# HF_AMP_DRIVER.net
KiCad netlist of a schematic drawn in Altium Designer
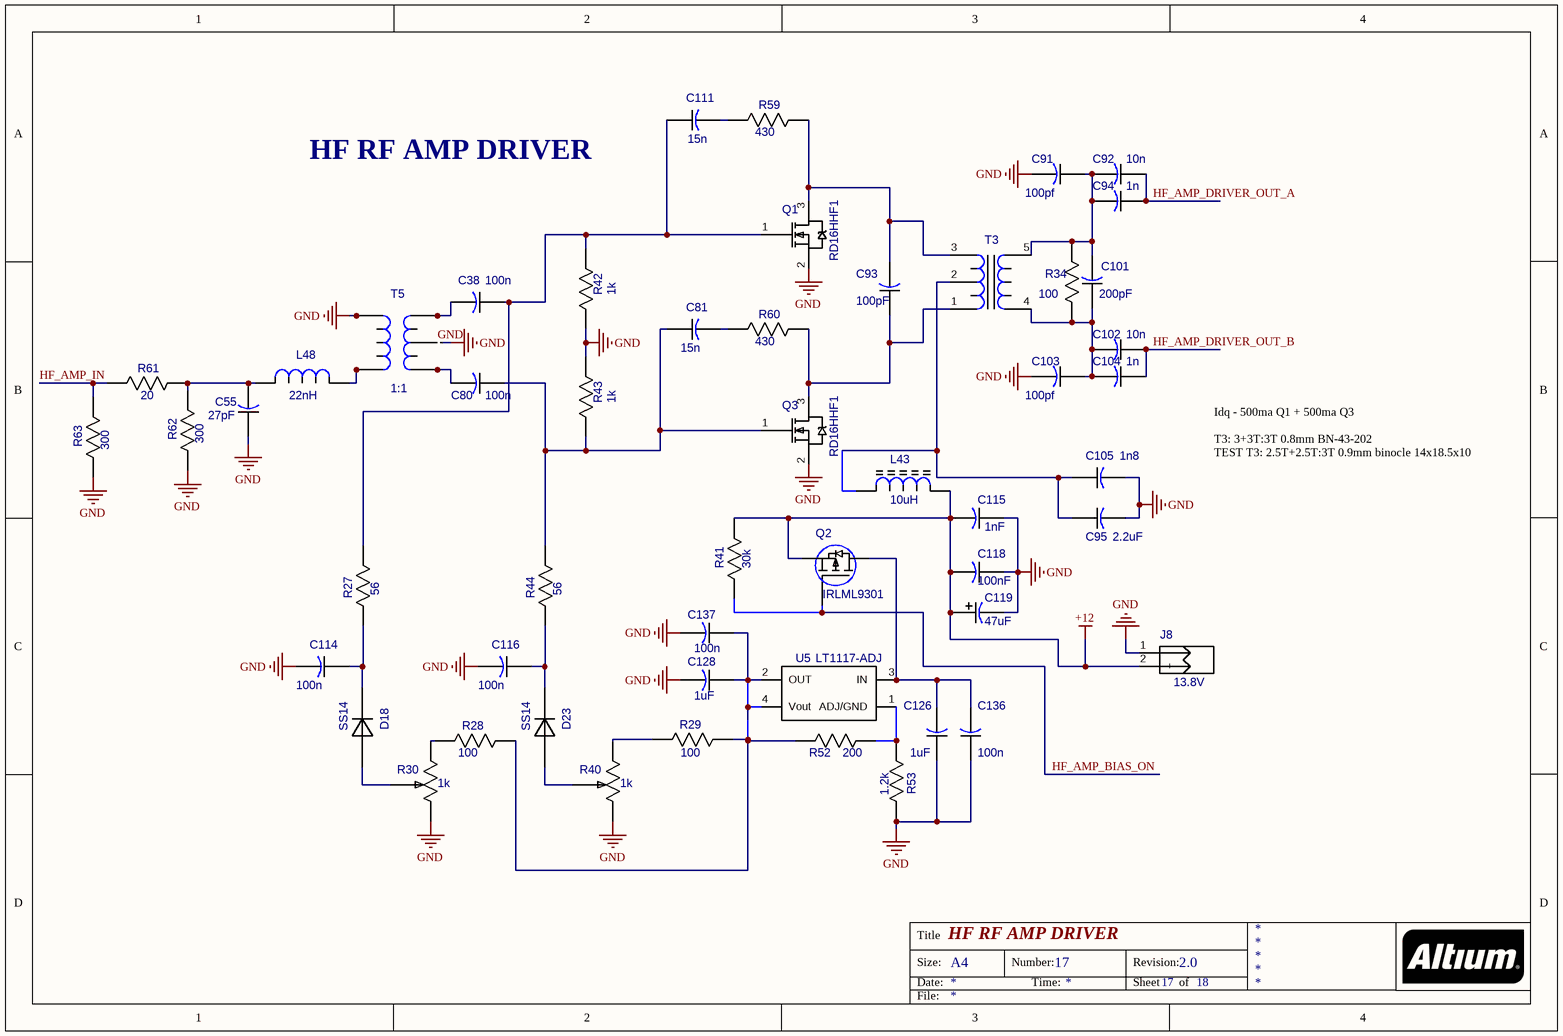
[diagram p0: HF_AMP_DRIVER.SchDoc]

(export (version "E")
  (design (tool "Eeschema 10.0.6"))
  (components
    (comp (ref "C38")
      (value "100n")
      (footprint "CAP_0805")
      (description "CAP_0805")
      (libsource (lib "*") (part "CAP_0805"))
    )
    (comp (ref "C55")
      (value "27pF")
      (footprint "CAP_0805")
      (description "CAP_0805")
      (libsource (lib "*") (part "CAP_0805"))
    )
    (comp (ref "C80")
      (value "100n")
      (footprint "CAP_0805")
      (description "CAP_0805")
      (libsource (lib "*") (part "CAP_0805"))
    )
    (comp (ref "C81")
      (value "15n")
      (footprint "CAP_1206")
      (description "CAP_1206")
      (libsource (lib "*") (part "CAP_1206"))
    )
    (comp (ref "C91")
      (value "100pf")
      (footprint "CAP_1206")
      (description "CAP_1206")
      (libsource (lib "*") (part "CAP_1206"))
    )
    (comp (ref "C92")
      (value "10n")
      (footprint "CAP_1206")
      (description "CAP_1206")
      (libsource (lib "*") (part "CAP_1206"))
    )
    (comp (ref "C93")
      (value "100pF")
      (footprint "CAP_1206")
      (description "CAP_1206")
      (libsource (lib "*") (part "CAP_1206"))
    )
    (comp (ref "C94")
      (value "1n")
      (footprint "CAP_1206")
      (description "CAP_1206")
      (libsource (lib "*") (part "CAP_1206"))
    )
    (comp (ref "C95")
      (value "2.2uF")
      (footprint "CAP_1206")
      (description "CAP_1206")
      (libsource (lib "*") (part "CAP_1206"))
    )
    (comp (ref "C101")
      (value "200pF")
      (footprint "CAP_1206")
      (description "CAP_1206")
      (libsource (lib "*") (part "CAP_1206"))
    )
    (comp (ref "C102")
      (value "10n")
      (footprint "CAP_1206")
      (description "CAP_1206")
      (libsource (lib "*") (part "CAP_1206"))
    )
    (comp (ref "C103")
      (value "100pf")
      (footprint "CAP_1206")
      (description "CAP_1206")
      (libsource (lib "*") (part "CAP_1206"))
    )
    (comp (ref "C104")
      (value "1n")
      (footprint "CAP_1206")
      (description "CAP_1206")
      (libsource (lib "*") (part "CAP_1206"))
    )
    (comp (ref "C105")
      (value "1n8")
      (footprint "CAP_1206")
      (description "CAP_1206")
      (libsource (lib "*") (part "CAP_1206"))
    )
    (comp (ref "C111")
      (value "15n")
      (footprint "CAP_1206")
      (description "CAP_1206")
      (libsource (lib "*") (part "CAP_1206"))
    )
    (comp (ref "C114")
      (value "100n")
      (footprint "CAP_0805")
      (description "CAP_0805")
      (libsource (lib "*") (part "CAP_0805"))
    )
    (comp (ref "C115")
      (value "1nF")
      (footprint "CAP_0805")
      (description "CAP_0805")
      (libsource (lib "*") (part "CAP_0805"))
    )
    (comp (ref "C116")
      (value "100n")
      (footprint "CAP_0805")
      (description "CAP_0805")
      (libsource (lib "*") (part "CAP_0805"))
    )
    (comp (ref "C118")
      (value "100nF")
      (footprint "CAP_0805")
      (description "CAP_0805")
      (libsource (lib "*") (part "CAP_0805"))
    )
    (comp (ref "C119")
      (value "47uF")
      (footprint "CAPAE_6.6x6.6h5.4")
      (description "CAPAE_6.6x6.6h5.4")
      (libsource (lib "*") (part "CAPAE_6.6x6.6h5.4"))
    )
    (comp (ref "C126")
      (value "1uF")
      (footprint "CAP_0805")
      (description "CAP_0805")
      (libsource (lib "*") (part "CAP_0805"))
    )
    (comp (ref "C128")
      (value "1uF")
      (footprint "CAP_0805")
      (description "CAP_0805")
      (libsource (lib "*") (part "CAP_0805"))
    )
    (comp (ref "C136")
      (value "100n")
      (footprint "CAP_0805")
      (description "CAP_0805")
      (libsource (lib "*") (part "CAP_0805"))
    )
    (comp (ref "C137")
      (value "100n")
      (footprint "CAP_0805")
      (description "CAP_0805")
      (libsource (lib "*") (part "CAP_0805"))
    )
    (comp (ref "D18") (value "SS14") (footprint "SS14") (libsource (lib "*") (part "SS14")))
    (comp (ref "D23") (value "SS14") (footprint "SS14") (libsource (lib "*") (part "SS14")))
    (comp (ref "J8")
      (value "13.8V")
      (footprint "1986717-2")
      (description "JX2")
      (libsource (lib "*") (part "1986717-2"))
    )
    (comp (ref "L43")
      (value "10uH")
      (footprint "IND_FERRITE_CORE")
      (description "Inductor")
      (libsource (lib "*") (part "IND_FERRITE_CORE"))
    )
    (comp (ref "L48")
      (value "22nH")
      (footprint "IND_0805")
      (description "IND_0805")
      (libsource (lib "*") (part "IND_0805"))
    )
    (comp (ref "Q1")
      (value "RD16HHF1")
      (footprint "RD16_V2")
      (libsource (lib "RF-UNIT-BIG") (part "RD16HHF1"))
    )
    (comp (ref "Q2")
      (value "IRLML9301")
      (footprint "SOT23")
      (description "MOSFET")
      (libsource (lib "*") (part "MOSFET_ENH_PD"))
    )
    (comp (ref "Q3")
      (value "RD16HHF1")
      (footprint "RD16_V2")
      (libsource (lib "RF-UNIT-BIG") (part "RD16HHF1"))
    )
    (comp (ref "R27")
      (value "56")
      (footprint "RES_0805")
      (description "RES_0805")
      (libsource (lib "*") (part "RES_0805"))
    )
    (comp (ref "R28")
      (value "100")
      (footprint "RES_0805")
      (description "RES_0805")
      (libsource (lib "*") (part "RES_0805"))
    )
    (comp (ref "R29")
      (value "100")
      (footprint "RES_0805")
      (description "RES_0805")
      (libsource (lib "*") (part "RES_0805"))
    )
    (comp (ref "R30")
      (value "1k")
      (footprint "306J")
      (description "306J")
      (fields (field (name "Comment") "ADJ-1k"))
      (libsource (lib "*") (part "306J"))
    )
    (comp (ref "R34")
      (value "100")
      (footprint "RES_1206")
      (description "RES_1206")
      (libsource (lib "*") (part "RES_1206"))
    )
    (comp (ref "R40")
      (value "1k")
      (footprint "306J")
      (description "306J")
      (fields (field (name "Comment") "ADJ-1k"))
      (libsource (lib "*") (part "306J"))
    )
    (comp (ref "R41")
      (value "30k")
      (footprint "RES_0805")
      (description "RES_0805")
      (libsource (lib "*") (part "RES_0805"))
    )
    (comp (ref "R42")
      (value "1k")
      (footprint "RES_0805")
      (description "RES_0805")
      (libsource (lib "*") (part "RES_0805"))
    )
    (comp (ref "R43")
      (value "1k")
      (footprint "RES_0805")
      (description "RES_0805")
      (libsource (lib "*") (part "RES_0805"))
    )
    (comp (ref "R44")
      (value "56")
      (footprint "RES_0805")
      (description "RES_0805")
      (libsource (lib "*") (part "RES_0805"))
    )
    (comp (ref "R52")
      (value "200")
      (footprint "RES_0805")
      (description "RES_0805")
      (libsource (lib "*") (part "RES_0805"))
    )
    (comp (ref "R53")
      (value "1.2k")
      (footprint "RES_0805")
      (description "RES_0805")
      (libsource (lib "*") (part "RES_0805"))
    )
    (comp (ref "R59")
      (value "430")
      (footprint "RES_1206")
      (description "RES_1206")
      (libsource (lib "*") (part "RES_1206"))
    )
    (comp (ref "R60")
      (value "430")
      (footprint "RES_1206")
      (description "RES_1206")
      (libsource (lib "*") (part "RES_1206"))
    )
    (comp (ref "R61")
      (value "20")
      (footprint "RES_1206")
      (description "RES_1206")
      (libsource (lib "*") (part "RES_1206"))
    )
    (comp (ref "R62")
      (value "300")
      (footprint "RES_1206")
      (description "RES_1206")
      (libsource (lib "*") (part "RES_1206"))
    )
    (comp (ref "R63")
      (value "300")
      (footprint "RES_1206")
      (description "RES_1206")
      (libsource (lib "*") (part "RES_1206"))
    )
    (comp (ref "T3")
      (value "TRANSF_HF3")
      (footprint "TRANSF_HF3")
      (libsource (lib "RF-UNIT-BIG") (part "TRANSF_RF3"))
    )
    (comp (ref "T5")
      (value "1:1")
      (footprint "TRANSF_ACORE2")
      (libsource (lib "RF-UNIT_1") (part "TRANSF_ACORE2"))
    )
    (comp (ref "U5")
      (value "LT1117-ADJ")
      (footprint "LT1117IST-ADJ")
      (description "LT1117IST-ADJ")
      (libsource (lib "*") (part "LT1117IST-ADJ"))
    )
  )
  (nets
    (net (code "1") (name "+12") (class "Default")
      (node (ref "C115") (pin "2") (pinfunction "2_2") (pintype "passive"))
      (node (ref "C118") (pin "2") (pinfunction "2_2") (pintype "passive"))
      (node (ref "C119") (pin "1") (pinfunction "PLUS_1") (pintype "passive"))
      (node (ref "J8") (pin "2") (pinfunction "+_2") (pintype "passive"))
      (node (ref "L43") (pin "2") (pinfunction "B_2") (pintype "passive"))
      (node (ref "Q2") (pin "2") (pinfunction "S_2") (pintype "passive"))
      (node (ref "R41") (pin "2") (pinfunction "2_2") (pintype "passive"))
    )
    (net (code "2") (name "/HF_AMP_BIAS_ON") (class "Default")
      (node (ref "Q2") (pin "1") (pinfunction "G_1") (pintype "passive"))
      (node (ref "R41") (pin "1") (pinfunction "1_1") (pintype "passive"))
    )
    (net (code "3") (name "/HF_AMP_DRIVER_OUT_A") (class "Default")
      (node (ref "C92") (pin "1") (pinfunction "1_1") (pintype "passive"))
      (node (ref "C94") (pin "1") (pinfunction "1_1") (pintype "passive"))
    )
    (net (code "4") (name "/HF_AMP_DRIVER_OUT_B") (class "Default")
      (node (ref "C102") (pin "1") (pinfunction "1_1") (pintype "passive"))
      (node (ref "C104") (pin "1") (pinfunction "1_1") (pintype "passive"))
    )
    (net (code "5") (name "/HF_AMP_IN") (class "Default")
      (node (ref "R61") (pin "1") (pinfunction "1_1") (pintype "passive"))
      (node (ref "R63") (pin "2") (pinfunction "2_2") (pintype "passive"))
    )
    (net (code "6") (name "GND") (class "Default")
      (node (ref "C103") (pin "2") (pinfunction "2_2") (pintype "passive"))
      (node (ref "C105") (pin "2") (pinfunction "2_2") (pintype "passive"))
      (node (ref "C114") (pin "2") (pinfunction "2_2") (pintype "passive"))
      (node (ref "C115") (pin "1") (pinfunction "1_1") (pintype "passive"))
      (node (ref "C116") (pin "2") (pinfunction "2_2") (pintype "passive"))
      (node (ref "C118") (pin "1") (pinfunction "1_1") (pintype "passive"))
      (node (ref "C119") (pin "2") (pinfunction "MINUS_2") (pintype "passive"))
      (node (ref "C126") (pin "1") (pinfunction "1_1") (pintype "passive"))
      (node (ref "C128") (pin "2") (pinfunction "2_2") (pintype "passive"))
      (node (ref "C136") (pin "1") (pinfunction "1_1") (pintype "passive"))
      (node (ref "C137") (pin "2") (pinfunction "2_2") (pintype "passive"))
      (node (ref "C55") (pin "1") (pinfunction "1_1") (pintype "passive"))
      (node (ref "C91") (pin "2") (pinfunction "2_2") (pintype "passive"))
      (node (ref "C95") (pin "2") (pinfunction "2_2") (pintype "passive"))
      (node (ref "J8") (pin "1") (pinfunction "-_1") (pintype "passive"))
      (node (ref "Q1") (pin "2") (pinfunction "S_2") (pintype "passive"))
      (node (ref "Q3") (pin "2") (pinfunction "S_2") (pintype "passive"))
      (node (ref "R30") (pin "1") (pinfunction "CCW_1") (pintype "passive"))
      (node (ref "R40") (pin "1") (pinfunction "CCW_1") (pintype "passive"))
      (node (ref "R42") (pin "1") (pinfunction "1_1") (pintype "passive"))
      (node (ref "R43") (pin "2") (pinfunction "2_2") (pintype "passive"))
      (node (ref "R53") (pin "2") (pinfunction "2_2") (pintype "passive"))
      (node (ref "R62") (pin "1") (pinfunction "1_1") (pintype "passive"))
      (node (ref "R63") (pin "1") (pinfunction "1_1") (pintype "passive"))
      (node (ref "T5") (pin "11") (pinfunction "0_11") (pintype "passive"))
      (node (ref "T5") (pin "2") (pinfunction "S2_2") (pintype "passive"))
      (node (ref "T5") (pin "4") (pinfunction "P2_4") (pintype "passive"))
      (node (ref "T5") (pin "8") (pinfunction "S2_8") (pintype "passive"))
    )
    (net (code "7") (name "Net-(C55-Pad2)") (class "Default")
      (node (ref "C55") (pin "2") (pinfunction "2_2") (pintype "passive"))
      (node (ref "L48") (pin "1") (pinfunction "1_1") (pintype "passive"))
      (node (ref "R61") (pin "2") (pinfunction "2_2") (pintype "passive"))
      (node (ref "R62") (pin "2") (pinfunction "2_2") (pintype "passive"))
    )
    (net (code "8") (name "Net-(C81-Pad2)") (class "Default")
      (node (ref "C81") (pin "2") (pinfunction "2_2") (pintype "passive"))
      (node (ref "R60") (pin "1") (pinfunction "1_1") (pintype "passive"))
    )
    (net (code "9") (name "Net-(C111-Pad2)") (class "Default")
      (node (ref "C111") (pin "2") (pinfunction "2_2") (pintype "passive"))
      (node (ref "R59") (pin "1") (pinfunction "1_1") (pintype "passive"))
    )
    (net (code "10") (name "Net-(D18-A)") (class "Default")
      (node (ref "D18") (pin "2") (pinfunction "A_2") (pintype "passive"))
      (node (ref "R30") (pin "2") (pinfunction "W_2") (pintype "passive"))
    )
    (net (code "11") (name "Net-(D18-K)") (class "Default")
      (node (ref "C114") (pin "1") (pinfunction "1_1") (pintype "passive"))
      (node (ref "D18") (pin "1") (pinfunction "K_1") (pintype "passive"))
      (node (ref "R27") (pin "1") (pinfunction "1_1") (pintype "passive"))
    )
    (net (code "12") (name "Net-(D23-A)") (class "Default")
      (node (ref "D23") (pin "2") (pinfunction "A_2") (pintype "passive"))
      (node (ref "R40") (pin "2") (pinfunction "W_2") (pintype "passive"))
    )
    (net (code "13") (name "Net-(D23-K)") (class "Default")
      (node (ref "C116") (pin "1") (pinfunction "1_1") (pintype "passive"))
      (node (ref "D23") (pin "1") (pinfunction "K_1") (pintype "passive"))
      (node (ref "R44") (pin "1") (pinfunction "1_1") (pintype "passive"))
    )
    (net (code "14") (name "Net-(L43-A)") (class "Default")
      (node (ref "C105") (pin "1") (pinfunction "1_1") (pintype "passive"))
      (node (ref "C95") (pin "1") (pinfunction "1_1") (pintype "passive"))
      (node (ref "L43") (pin "1") (pinfunction "A_1") (pintype "passive"))
      (node (ref "T3") (pin "2") (pinfunction "S3_2") (pintype "passive"))
    )
    (net (code "15") (name "Net-(Q1-D)") (class "Default")
      (node (ref "C93") (pin "2") (pinfunction "2_2") (pintype "passive"))
      (node (ref "Q1") (pin "3") (pinfunction "D_3") (pintype "passive"))
      (node (ref "R59") (pin "2") (pinfunction "2_2") (pintype "passive"))
      (node (ref "T3") (pin "3") (pinfunction "S1_3") (pintype "passive"))
    )
    (net (code "16") (name "Net-(Q1-G)") (class "Default")
      (node (ref "C111") (pin "1") (pinfunction "1_1") (pintype "passive"))
      (node (ref "C38") (pin "1") (pinfunction "1_1") (pintype "passive"))
      (node (ref "Q1") (pin "1") (pinfunction "G_1") (pintype "passive"))
      (node (ref "R27") (pin "2") (pinfunction "2_2") (pintype "passive"))
      (node (ref "R42") (pin "2") (pinfunction "2_2") (pintype "passive"))
    )
    (net (code "17") (name "Net-(Q2-D)") (class "Default")
      (node (ref "C126") (pin "2") (pinfunction "2_2") (pintype "passive"))
      (node (ref "C136") (pin "2") (pinfunction "2_2") (pintype "passive"))
      (node (ref "Q2") (pin "3") (pinfunction "D_3") (pintype "passive"))
      (node (ref "U5") (pin "3") (pinfunction "IN_3") (pintype "passive"))
    )
    (net (code "18") (name "Net-(Q3-D)") (class "Default")
      (node (ref "C93") (pin "1") (pinfunction "1_1") (pintype "passive"))
      (node (ref "Q3") (pin "3") (pinfunction "D_3") (pintype "passive"))
      (node (ref "R60") (pin "2") (pinfunction "2_2") (pintype "passive"))
      (node (ref "T3") (pin "1") (pinfunction "S2_1") (pintype "passive"))
    )
    (net (code "19") (name "Net-(Q3-G)") (class "Default")
      (node (ref "C80") (pin "1") (pinfunction "1_1") (pintype "passive"))
      (node (ref "C81") (pin "1") (pinfunction "1_1") (pintype "passive"))
      (node (ref "Q3") (pin "1") (pinfunction "G_1") (pintype "passive"))
      (node (ref "R43") (pin "1") (pinfunction "1_1") (pintype "passive"))
      (node (ref "R44") (pin "2") (pinfunction "2_2") (pintype "passive"))
    )
    (net (code "20") (name "Net-(R30-CW)") (class "Default")
      (node (ref "R28") (pin "1") (pinfunction "1_1") (pintype "passive"))
      (node (ref "R30") (pin "3") (pinfunction "CW_3") (pintype "passive"))
    )
    (net (code "21") (name "Net-(R40-CW)") (class "Default")
      (node (ref "R29") (pin "1") (pinfunction "1_1") (pintype "passive"))
      (node (ref "R40") (pin "3") (pinfunction "CW_3") (pintype "passive"))
    )
    (net (code "22") (name "Net-(T3-P1)") (class "Default")
      (node (ref "C101") (pin "2") (pinfunction "2_2") (pintype "passive"))
      (node (ref "C91") (pin "1") (pinfunction "1_1") (pintype "passive"))
      (node (ref "C92") (pin "2") (pinfunction "2_2") (pintype "passive"))
      (node (ref "C94") (pin "2") (pinfunction "2_2") (pintype "passive"))
      (node (ref "R34") (pin "2") (pinfunction "2_2") (pintype "passive"))
      (node (ref "T3") (pin "5") (pinfunction "P1_5") (pintype "passive"))
    )
    (net (code "23") (name "Net-(T3-P2)") (class "Default")
      (node (ref "C101") (pin "1") (pinfunction "1_1") (pintype "passive"))
      (node (ref "C102") (pin "2") (pinfunction "2_2") (pintype "passive"))
      (node (ref "C103") (pin "1") (pinfunction "1_1") (pintype "passive"))
      (node (ref "C104") (pin "2") (pinfunction "2_2") (pintype "passive"))
      (node (ref "R34") (pin "1") (pinfunction "1_1") (pintype "passive"))
      (node (ref "T3") (pin "4") (pinfunction "P2_4") (pintype "passive"))
    )
    (net (code "24") (name "Net-(T5-P1)") (class "Default")
      (node (ref "L48") (pin "2") (pinfunction "2_2") (pintype "passive"))
      (node (ref "T5") (pin "10") (pinfunction "0_10") (pintype "passive"))
      (node (ref "T5") (pin "6") (pinfunction "P1_6") (pintype "passive"))
    )
    (net (code "25") (name "Net-(T5-S1)") (class "Default")
      (node (ref "C80") (pin "2") (pinfunction "2_2") (pintype "passive"))
      (node (ref "T5") (pin "1") (pinfunction "S1_1") (pintype "passive"))
      (node (ref "T5") (pin "7") (pinfunction "0_7") (pintype "passive"))
    )
    (net (code "26") (name "Net-(T5-S3)") (class "Default")
      (node (ref "C38") (pin "2") (pinfunction "2_2") (pintype "passive"))
      (node (ref "T5") (pin "3") (pinfunction "S3_3") (pintype "passive"))
      (node (ref "T5") (pin "9") (pinfunction "0_9") (pintype "passive"))
    )
    (net (code "27") (name "Net-(U5-ADJ{slash}GND)") (class "Default")
      (node (ref "R52") (pin "2") (pinfunction "2_2") (pintype "passive"))
      (node (ref "R53") (pin "1") (pinfunction "1_1") (pintype "passive"))
      (node (ref "U5") (pin "1") (pinfunction "ADJ/GND_1") (pintype "passive"))
    )
    (net (code "28") (name "Net-(U5-OUT)") (class "Default")
      (node (ref "C128") (pin "1") (pinfunction "1_1") (pintype "passive"))
      (node (ref "C137") (pin "1") (pinfunction "1_1") (pintype "passive"))
      (node (ref "R28") (pin "2") (pinfunction "2_2") (pintype "passive"))
      (node (ref "R29") (pin "2") (pinfunction "2_2") (pintype "passive"))
      (node (ref "R52") (pin "1") (pinfunction "1_1") (pintype "passive"))
      (node (ref "U5") (pin "2") (pinfunction "OUT_2") (pintype "passive"))
      (node (ref "U5") (pin "4") (pinfunction "Vout_4") (pintype "passive"))
    )
  )
)
